# Schema.net
KiCad netlist of a schematic drawn in Altium Designer
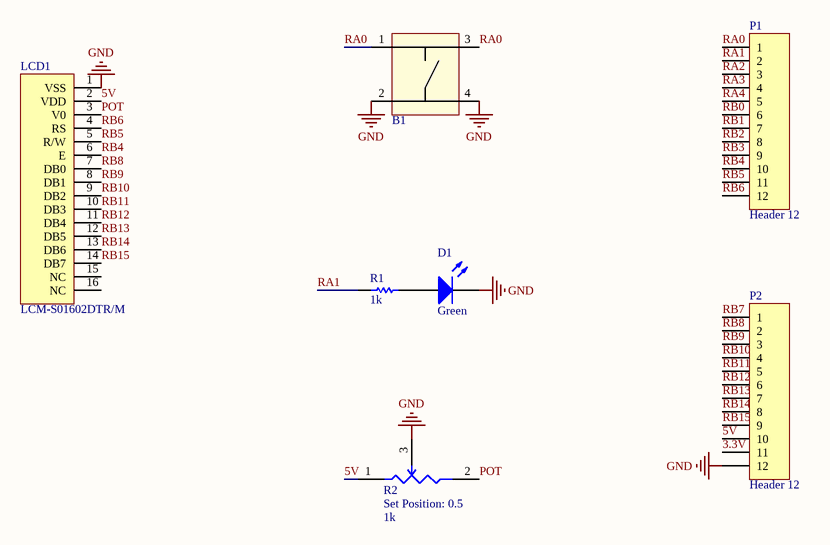
[diagram p0: Schema.SchDoc]

(export (version "E")
  (design (tool "Eeschema 10.0.6"))
  (components
    (comp (ref "B1")
      (value "BoutonPoussoir")
      (footprint "BoutonPoussoirMini")
      (description "Switch Tactile SPST-NO")
      (libsource (lib "AnalogDevices") (part "BoutonPoussoir"))
    )
    (comp (ref "D1")
      (value "LED_GREEN")
      (footprint "LED_GREEN")
      (description "Typical Green LED")
      (fields (field (name "COLOR") "Green") (field (name "PUBLISHER") "Altium Limited"))
      (libsource (lib "AnalogDevices") (part "LED_GREEN"))
    )
    (comp (ref "LCD1")
      (value "LCM-S01602DTR/M")
      (footprint "LCM-S01602DTR/M")
      (description "LCD MODULE 16X2 CHARACTER")
      (fields (field (name "PUBLISHER") "Altium Limited"))
      (libsource (lib "IntegratedCircuits") (part "LCM-S01602DTR/M"))
    )
    (comp (ref "P1")
      (value "Header 12")
      (footprint "HDR1X12")
      (description "Header, 12-Pin")
      (fields (field (name "PUBLISHER") "Altium Limited"))
      (libsource (lib "Connectors") (part "Header 12"))
    )
    (comp (ref "P2")
      (value "Header 12")
      (footprint "HDR1X12")
      (description "Header, 12-Pin")
      (fields (field (name "PUBLISHER") "Altium Limited"))
      (libsource (lib "Connectors") (part "Header 12"))
    )
    (comp (ref "R1")
      (value "1k")
      (footprint "RES1206R")
      (description "Resistor")
      (fields (field (name "Comment") "Res") (field (name "PUBLISHER") "Altium Limited"))
      (libsource (lib "Resistors") (part "Res"))
    )
    (comp (ref "R2")
      (value "1k")
      (footprint "Potentiometer")
      (description "Potentiometer")
      (fields
        (field (name "SET POSITION") "0.5")
        (field (name "Comment") "ResVar")
        (field (name "PUBLISHER") "Altium Limited")
      )
      (libsource (lib "AnalogDevices") (part "ResVar"))
    )
  )
  (nets
    (net (code "1") (name "/3.3V") (class "Default")
      (node (ref "P2") (pin "11") (pinfunction "11_11") (pintype "passive"))
    )
    (net (code "2") (name "/5V") (class "Default")
      (node (ref "LCD1") (pin "2") (pinfunction "VDD_2") (pintype "passive"))
      (node (ref "P2") (pin "10") (pinfunction "10_10") (pintype "passive"))
      (node (ref "R2") (pin "1") (pinfunction "CCW_1") (pintype "passive"))
    )
    (net (code "3") (name "/POT") (class "Default")
      (node (ref "LCD1") (pin "3") (pinfunction "V0_3") (pintype "passive"))
      (node (ref "R2") (pin "2") (pinfunction "CW_2") (pintype "passive"))
    )
    (net (code "4") (name "/RA0") (class "Default")
      (node (ref "B1") (pin "1") (pinfunction "1_1") (pintype "passive"))
      (node (ref "B1") (pin "3") (pinfunction "3_3") (pintype "passive"))
      (node (ref "P1") (pin "1") (pinfunction "1_1") (pintype "passive"))
    )
    (net (code "5") (name "/RA1") (class "Default")
      (node (ref "P1") (pin "2") (pinfunction "2_2") (pintype "passive"))
      (node (ref "R1") (pin "1") (pinfunction "1_1") (pintype "passive"))
    )
    (net (code "6") (name "/RA2") (class "Default")
      (node (ref "P1") (pin "3") (pinfunction "3_3") (pintype "passive"))
    )
    (net (code "7") (name "/RA3") (class "Default")
      (node (ref "P1") (pin "4") (pinfunction "4_4") (pintype "passive"))
    )
    (net (code "8") (name "/RA4") (class "Default")
      (node (ref "P1") (pin "5") (pinfunction "5_5") (pintype "passive"))
    )
    (net (code "9") (name "/RB0") (class "Default")
      (node (ref "P1") (pin "6") (pinfunction "6_6") (pintype "passive"))
    )
    (net (code "10") (name "/RB1") (class "Default")
      (node (ref "P1") (pin "7") (pinfunction "7_7") (pintype "passive"))
    )
    (net (code "11") (name "/RB2") (class "Default")
      (node (ref "P1") (pin "8") (pinfunction "8_8") (pintype "passive"))
    )
    (net (code "12") (name "/RB3") (class "Default")
      (node (ref "P1") (pin "9") (pinfunction "9_9") (pintype "passive"))
    )
    (net (code "13") (name "/RB4") (class "Default")
      (node (ref "LCD1") (pin "6") (pinfunction "E_6") (pintype "passive"))
      (node (ref "P1") (pin "10") (pinfunction "10_10") (pintype "passive"))
    )
    (net (code "14") (name "/RB5") (class "Default")
      (node (ref "LCD1") (pin "5") (pinfunction "R/W_5") (pintype "passive"))
      (node (ref "P1") (pin "11") (pinfunction "11_11") (pintype "passive"))
    )
    (net (code "15") (name "/RB6") (class "Default")
      (node (ref "LCD1") (pin "4") (pinfunction "RS_4") (pintype "passive"))
      (node (ref "P1") (pin "12") (pinfunction "12_12") (pintype "passive"))
    )
    (net (code "16") (name "/RB7") (class "Default")
      (node (ref "P2") (pin "1") (pinfunction "1_1") (pintype "passive"))
    )
    (net (code "17") (name "/RB8") (class "Default")
      (node (ref "LCD1") (pin "7") (pinfunction "DB0_7") (pintype "passive"))
      (node (ref "P2") (pin "2") (pinfunction "2_2") (pintype "passive"))
    )
    (net (code "18") (name "/RB9") (class "Default")
      (node (ref "LCD1") (pin "8") (pinfunction "DB1_8") (pintype "passive"))
      (node (ref "P2") (pin "3") (pinfunction "3_3") (pintype "passive"))
    )
    (net (code "19") (name "/RB10") (class "Default")
      (node (ref "LCD1") (pin "9") (pinfunction "DB2_9") (pintype "passive"))
      (node (ref "P2") (pin "4") (pinfunction "4_4") (pintype "passive"))
    )
    (net (code "20") (name "/RB11") (class "Default")
      (node (ref "LCD1") (pin "10") (pinfunction "DB3_10") (pintype "passive"))
      (node (ref "P2") (pin "5") (pinfunction "5_5") (pintype "passive"))
    )
    (net (code "21") (name "/RB12") (class "Default")
      (node (ref "LCD1") (pin "11") (pinfunction "DB4_11") (pintype "passive"))
      (node (ref "P2") (pin "6") (pinfunction "6_6") (pintype "passive"))
    )
    (net (code "22") (name "/RB13") (class "Default")
      (node (ref "LCD1") (pin "12") (pinfunction "DB5_12") (pintype "passive"))
      (node (ref "P2") (pin "7") (pinfunction "7_7") (pintype "passive"))
    )
    (net (code "23") (name "/RB14") (class "Default")
      (node (ref "LCD1") (pin "13") (pinfunction "DB6_13") (pintype "passive"))
      (node (ref "P2") (pin "8") (pinfunction "8_8") (pintype "passive"))
    )
    (net (code "24") (name "/RB15") (class "Default")
      (node (ref "LCD1") (pin "14") (pinfunction "DB7_14") (pintype "passive"))
      (node (ref "P2") (pin "9") (pinfunction "9_9") (pintype "passive"))
    )
    (net (code "25") (name "GND") (class "Default")
      (node (ref "B1") (pin "2") (pinfunction "2_2") (pintype "passive"))
      (node (ref "B1") (pin "4") (pinfunction "4_4") (pintype "passive"))
      (node (ref "D1") (pin "2") (pinfunction "K_2") (pintype "passive"))
      (node (ref "LCD1") (pin "1") (pinfunction "VSS_1") (pintype "passive"))
      (node (ref "P2") (pin "12") (pinfunction "12_12") (pintype "passive"))
      (node (ref "R2") (pin "3") (pinfunction "Wiper_3") (pintype "passive"))
    )
    (net (code "26") (name "Net-(D1-A)") (class "Default")
      (node (ref "D1") (pin "1") (pinfunction "A_1") (pintype "passive"))
      (node (ref "R1") (pin "2") (pinfunction "2_2") (pintype "passive"))
    )
    (net (code "27") (name "unconnected-(LCD1-NC-Pad15)") (class "Default")
      (node (ref "LCD1") (pin "15") (pinfunction "NC_15") (pintype "passive"))
    )
    (net (code "28") (name "unconnected-(LCD1-NC-Pad16)") (class "Default")
      (node (ref "LCD1") (pin "16") (pinfunction "NC_16") (pintype "passive"))
    )
  )
)
